# RoverWing-V095.net
KiCad netlist of a schematic drawn in EAGLE
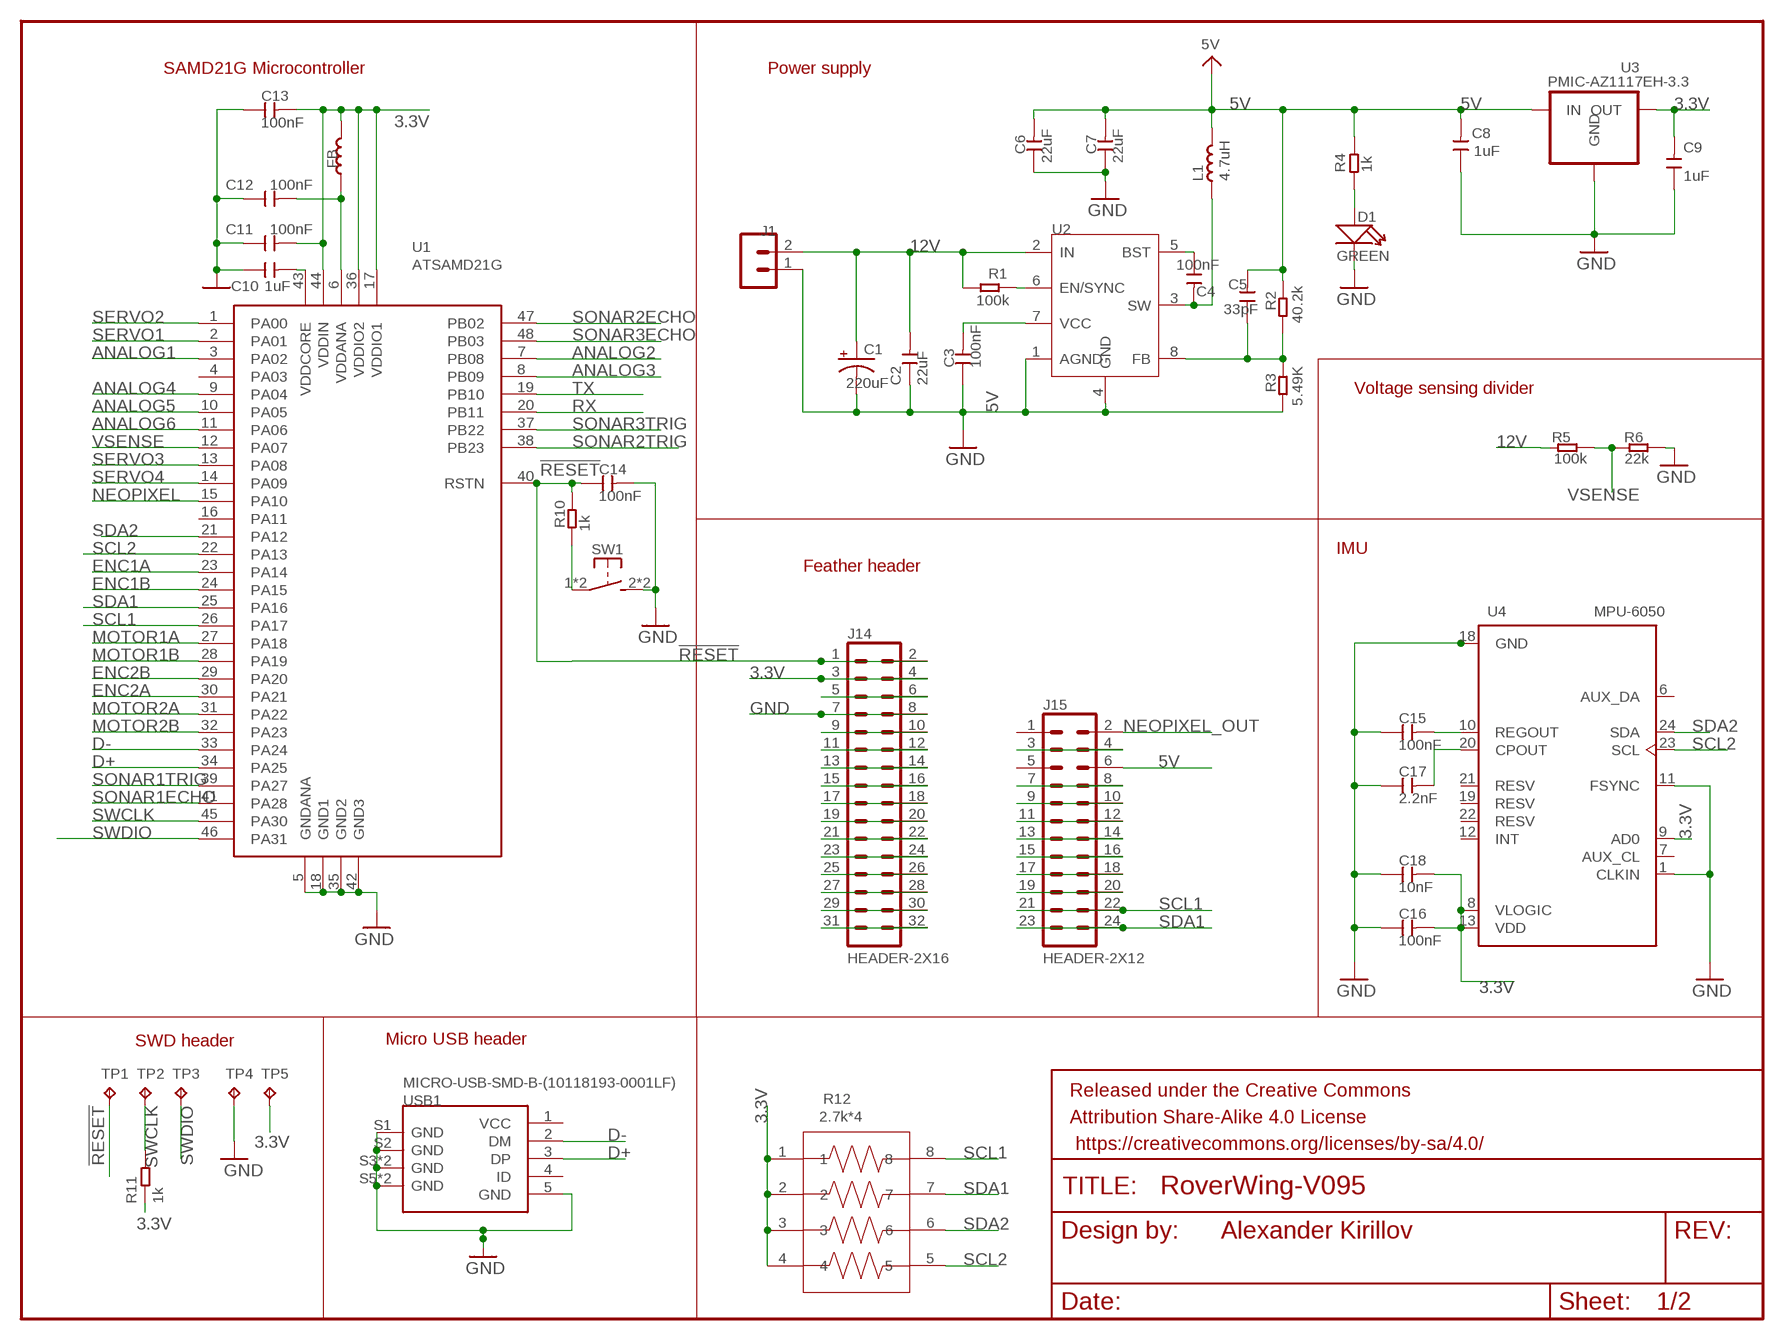
[diagram p0: schematic, sheet 1]
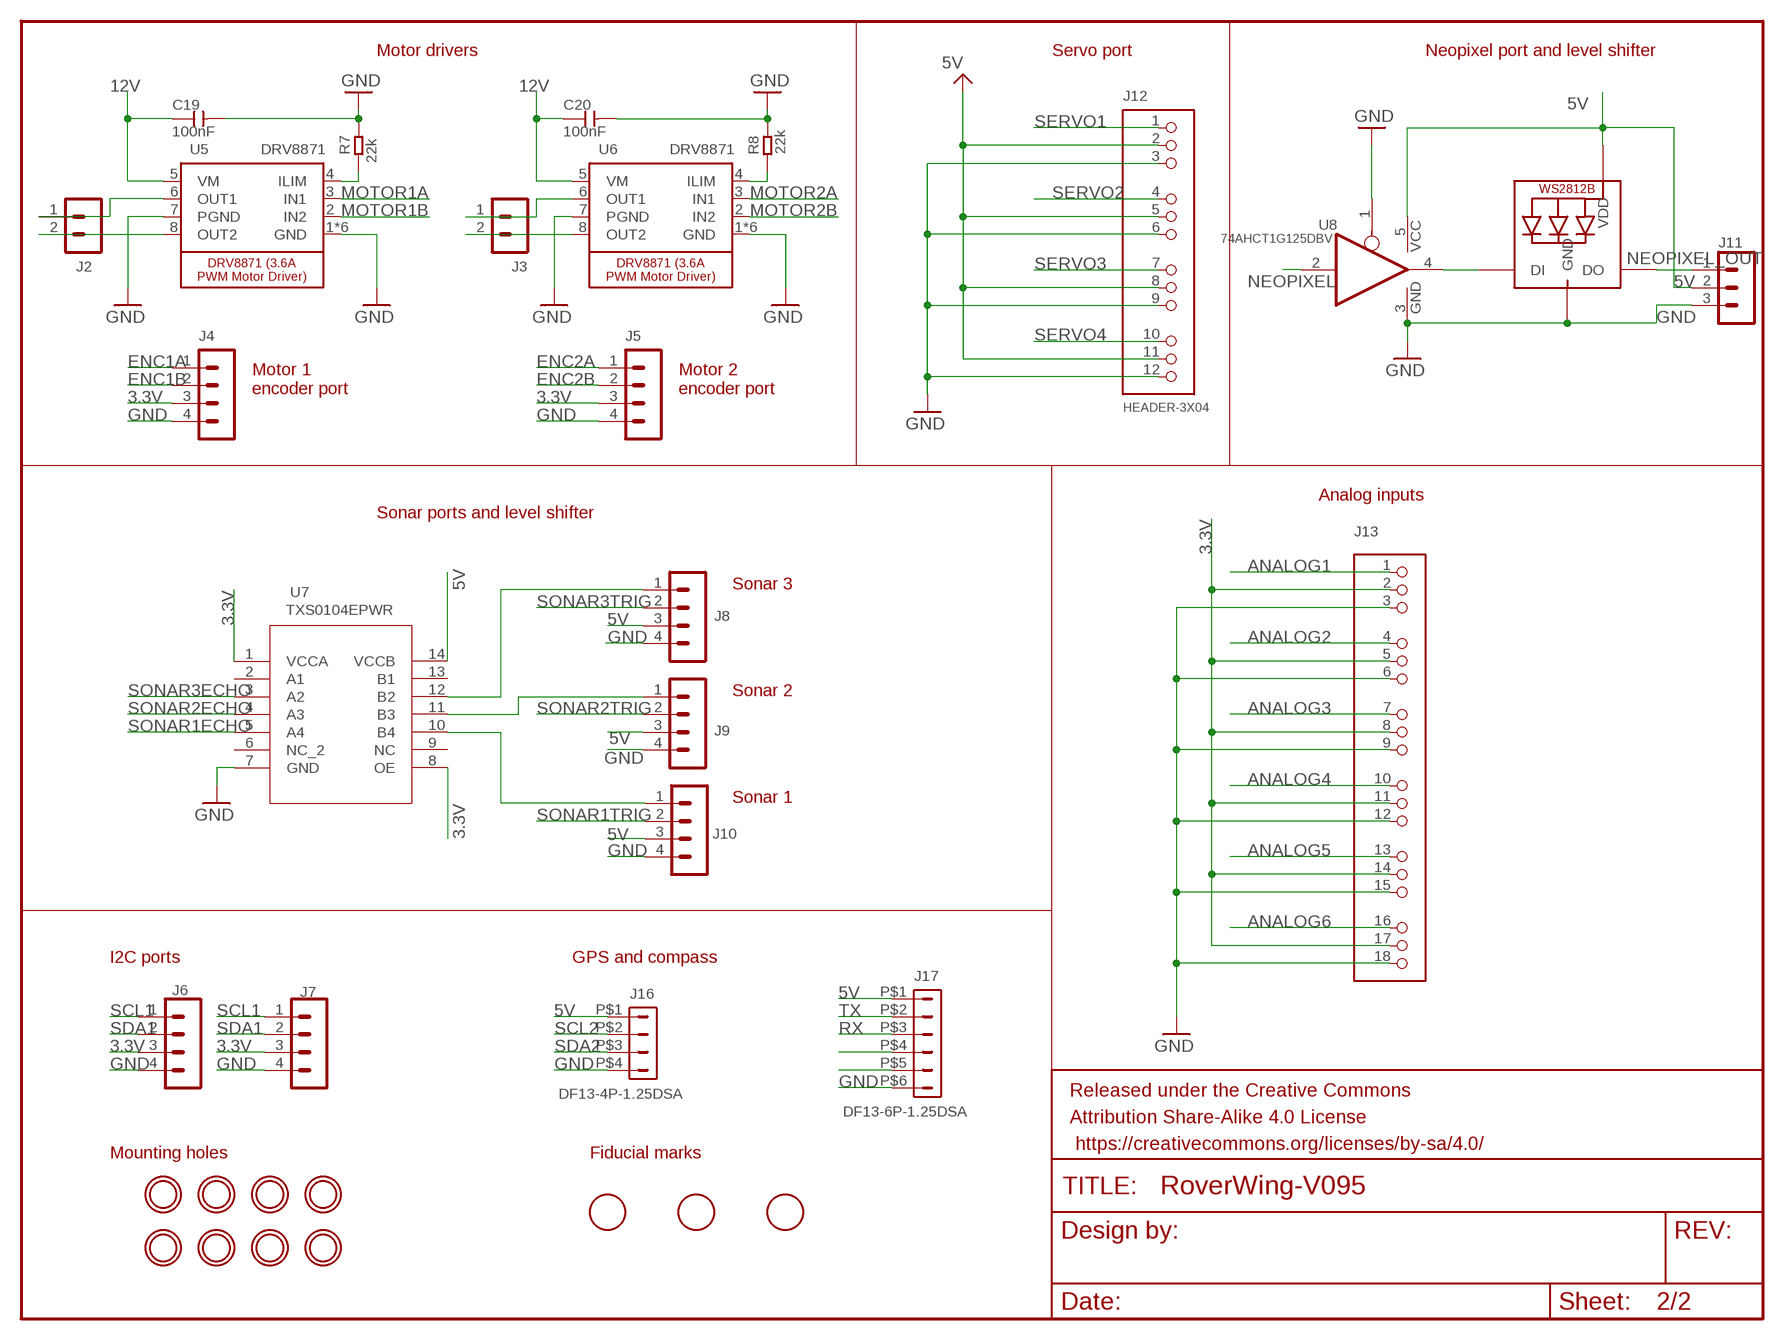
[diagram p1: schematic, sheet 2]

(export (version "E")
  (design (tool "Eeschema 10.0.6"))
  (components
    (comp (ref "C19")
      (value "100nF")
      (footprint "eagle-import:0805")
      (libsource (lib "eagle-import") (part "CAP-CERAMIC-SMD0805"))
    )
    (comp (ref "C20")
      (value "100nF")
      (footprint "eagle-import:0805")
      (libsource (lib "eagle-import") (part "CAP-CERAMIC-SMD0805"))
    )
    (comp (ref "FRAME1")
      (value "FRAME-LETTERNO_PACKAGE")
      (footprint "eagle-import:DUMMY")
      (libsource (lib "eagle-import") (part "FRAME-LETTERNO_PACKAGE"))
    )
    (comp (ref "J2")
      (value "HEADER-VH")
      (footprint "eagle-import:B2P-VH")
      (fields (field (name "PARTNO") "B2P-VH(LF)(SN)  "))
      (libsource (lib "eagle-import") (part "HEADER-VH"))
    )
    (comp (ref "J3")
      (value "HEADER-VH")
      (footprint "eagle-import:B2P-VH")
      (fields (field (name "PARTNO") "B2P-VH(LF)(SN)  "))
      (libsource (lib "eagle-import") (part "HEADER-VH"))
    )
    (comp (ref "J4")
      (value "HEADER-PH-4P")
      (footprint "eagle-import:B4B-PH-K")
      (fields (field (name "PARTNO") "B4B-PH-K-S(LF)(SN)"))
      (libsource (lib "eagle-import") (part "HEADER-PH-4P"))
    )
    (comp (ref "J5")
      (value "HEADER-PH-4P")
      (footprint "eagle-import:B4B-PH-K")
      (fields (field (name "PARTNO") "B4B-PH-K-S(LF)(SN)"))
      (libsource (lib "eagle-import") (part "HEADER-PH-4P"))
    )
    (comp (ref "J6")
      (value "HEADER-PH-4P")
      (footprint "eagle-import:B4B-PH-K")
      (fields (field (name "PARTNO") "B4B-PH-K-S(LF)(SN)"))
      (libsource (lib "eagle-import") (part "HEADER-PH-4P"))
    )
    (comp (ref "J7")
      (value "HEADER-PH-4P")
      (footprint "eagle-import:B4B-PH-K")
      (fields (field (name "PARTNO") "B4B-PH-K-S(LF)(SN)"))
      (libsource (lib "eagle-import") (part "HEADER-PH-4P"))
    )
    (comp (ref "J8")
      (value "HEADER-PH-4P")
      (footprint "eagle-import:B4B-PH-K")
      (fields (field (name "PARTNO") "B4B-PH-K-S(LF)(SN)"))
      (libsource (lib "eagle-import") (part "HEADER-PH-4P"))
    )
    (comp (ref "J9")
      (value "HEADER-PH-4P")
      (footprint "eagle-import:B4B-PH-K")
      (fields (field (name "PARTNO") "B4B-PH-K-S(LF)(SN)"))
      (libsource (lib "eagle-import") (part "HEADER-PH-4P"))
    )
    (comp (ref "J10")
      (value "HEADER-PH-4P")
      (footprint "eagle-import:B4B-PH-K")
      (fields (field (name "PARTNO") "B4B-PH-K-S(LF)(SN)"))
      (libsource (lib "eagle-import") (part "HEADER-PH-4P"))
    )
    (comp (ref "J11")
      (value "HEADER-PH-3P")
      (footprint "eagle-import:B3B-PH-K")
      (fields (field (name "PARTNO") "B3B-PH-K-S(LF)(SN)"))
      (libsource (lib "eagle-import") (part "HEADER-PH-3P"))
    )
    (comp (ref "J12")
      (value "HEADER-3X04")
      (footprint "eagle-import:3X04")
      (libsource (lib "eagle-import") (part "HEADER-3X04"))
    )
    (comp (ref "J13")
      (value "HEADER-3X06\"")
      (footprint "eagle-import:3X06")
      (libsource (lib "eagle-import") (part "HEADER-3X06{dblquote}"))
    )
    (comp (ref "J16")
      (value "DF13-4P-1.25DSA")
      (footprint "eagle-import:DF13-4P-1.25DSA")
      (libsource (lib "eagle-import") (part "DF13-4P-1.25DSA"))
    )
    (comp (ref "J17")
      (value "DF13-6P-1.25DSA")
      (footprint "eagle-import:DF13-6P-1.25DSA")
      (libsource (lib "eagle-import") (part "DF13-6P-1.25DSA"))
    )
    (comp (ref "LED1")
      (value "WS2812B3535")
      (footprint "eagle-import:LED3535")
      (fields (field (name "MANUFACTURER") "Worldsemi") (field (name "PARTNO") "WS2812B-3535 "))
      (libsource (lib "eagle-import") (part "WS2812B3535"))
    )
    (comp (ref "R7")
      (value "22k")
      (footprint "eagle-import:0805")
      (libsource (lib "eagle-import") (part "RES-SMD-0805"))
    )
    (comp (ref "R8")
      (value "22k")
      (footprint "eagle-import:0805")
      (libsource (lib "eagle-import") (part "RES-SMD-0805"))
    )
    (comp (ref "U$3")
      (value "MOUNTINGHOLE3.0_NPH")
      (footprint "eagle-import:MOUNTINGHOLE_3.0_NPH")
      (libsource (lib "eagle-import") (part "MOUNTINGHOLE3.0_NPH"))
    )
    (comp (ref "U$4")
      (value "MOUNTINGHOLE3.0_NPH")
      (footprint "eagle-import:MOUNTINGHOLE_3.0_NPH")
      (libsource (lib "eagle-import") (part "MOUNTINGHOLE3.0_NPH"))
    )
    (comp (ref "U$11")
      (value "FIDUCIAL")
      (footprint "eagle-import:FIDUCIAL_1MM")
      (libsource (lib "eagle-import") (part "FIDUCIAL"))
    )
    (comp (ref "U$13")
      (value "FIDUCIAL")
      (footprint "eagle-import:FIDUCIAL_1MM")
      (libsource (lib "eagle-import") (part "FIDUCIAL"))
    )
    (comp (ref "U$14")
      (value "MOUNTINGHOLE3.0_NPH")
      (footprint "eagle-import:MOUNTINGHOLE_3.0_NPH")
      (libsource (lib "eagle-import") (part "MOUNTINGHOLE3.0_NPH"))
    )
    (comp (ref "U$15")
      (value "MOUNTINGHOLE3.0_NPH")
      (footprint "eagle-import:MOUNTINGHOLE_3.0_NPH")
      (libsource (lib "eagle-import") (part "MOUNTINGHOLE3.0_NPH"))
    )
    (comp (ref "U$17")
      (value "FIDUCIAL")
      (footprint "eagle-import:FIDUCIAL_1MM")
      (libsource (lib "eagle-import") (part "FIDUCIAL"))
    )
    (comp (ref "U$24")
      (value "MOUNTINGHOLE3.0_NPH")
      (footprint "eagle-import:MOUNTINGHOLE_3.0_NPH")
      (libsource (lib "eagle-import") (part "MOUNTINGHOLE3.0_NPH"))
    )
    (comp (ref "U$25")
      (value "MOUNTINGHOLE3.0_NPH")
      (footprint "eagle-import:MOUNTINGHOLE_3.0_NPH")
      (libsource (lib "eagle-import") (part "MOUNTINGHOLE3.0_NPH"))
    )
    (comp (ref "U$26")
      (value "MOUNTINGHOLE3.0_NPH")
      (footprint "eagle-import:MOUNTINGHOLE_3.0_NPH")
      (libsource (lib "eagle-import") (part "MOUNTINGHOLE3.0_NPH"))
    )
    (comp (ref "U$27")
      (value "MOUNTINGHOLE3.0_NPH")
      (footprint "eagle-import:MOUNTINGHOLE_3.0_NPH")
      (libsource (lib "eagle-import") (part "MOUNTINGHOLE3.0_NPH"))
    )
    (comp (ref "U5")
      (value "DRV8871")
      (footprint "eagle-import:HSOP8")
      (fields (field (name "MANUFACTURER") "TEXAS INSTRUMENTS") (field (name "PARTNO") "DRV8871DDAR"))
      (libsource (lib "eagle-import") (part "DRV8871"))
    )
    (comp (ref "U6")
      (value "DRV8871")
      (footprint "eagle-import:HSOP8")
      (fields (field (name "MANUFACTURER") "TEXAS INSTRUMENTS") (field (name "PARTNO") "DRV8871DDAR"))
      (libsource (lib "eagle-import") (part "DRV8871"))
    )
    (comp (ref "U7")
      (value "TXS0104EPWR")
      (footprint "eagle-import:PW14")
      (fields (field (name "MANUFACTURER") "Texas Instruments"))
      (libsource (lib "eagle-import") (part "TXS0104EPWR"))
    )
    (comp (ref "U8")
      (value "74AHCT1G125DBV")
      (footprint "eagle-import:SOT23-5")
      (fields (field (name "PARTNO") "SN74AHCT1G125DBVR"))
      (libsource (lib "eagle-import") (part "741G125DBVAHCT"))
    )
    (comp (ref "C1")
      (value "220uF")
      (footprint "eagle-import:CAP-8X10.5")
      (libsource (lib "eagle-import") (part "CAP-POL-SMD-8X10.5"))
    )
    (comp (ref "C2")
      (value "22uF")
      (footprint "eagle-import:0805")
      (libsource (lib "eagle-import") (part "CAP-CERAMIC-SMD0805"))
    )
    (comp (ref "C3")
      (value "100nF")
      (footprint "eagle-import:0805")
      (libsource (lib "eagle-import") (part "CAP-CERAMIC-SMD0805"))
    )
    (comp (ref "C4")
      (value "100nF")
      (footprint "eagle-import:0805")
      (libsource (lib "eagle-import") (part "CAP-CERAMIC-SMD0805"))
    )
    (comp (ref "C5")
      (value "33pF")
      (footprint "eagle-import:0805")
      (libsource (lib "eagle-import") (part "CAP-CERAMIC-SMD0805"))
    )
    (comp (ref "C6")
      (value "22uF")
      (footprint "eagle-import:0805")
      (libsource (lib "eagle-import") (part "CAP-CERAMIC-SMD0805"))
    )
    (comp (ref "C7")
      (value "22uF")
      (footprint "eagle-import:0805")
      (libsource (lib "eagle-import") (part "CAP-CERAMIC-SMD0805"))
    )
    (comp (ref "C8")
      (value "1uF")
      (footprint "eagle-import:0805")
      (libsource (lib "eagle-import") (part "CAP-CERAMIC-SMD0805"))
    )
    (comp (ref "C9")
      (value "1uF")
      (footprint "eagle-import:0805")
      (libsource (lib "eagle-import") (part "CAP-CERAMIC-SMD0805"))
    )
    (comp (ref "C10")
      (value "1uF")
      (footprint "eagle-import:0805")
      (libsource (lib "eagle-import") (part "CAP-CERAMIC-SMD0805"))
    )
    (comp (ref "C11")
      (value "100nF")
      (footprint "eagle-import:0805")
      (libsource (lib "eagle-import") (part "CAP-CERAMIC-SMD0805"))
    )
    (comp (ref "C12")
      (value "100nF")
      (footprint "eagle-import:0805")
      (libsource (lib "eagle-import") (part "CAP-CERAMIC-SMD0805"))
    )
    (comp (ref "C13")
      (value "100nF")
      (footprint "eagle-import:0805")
      (libsource (lib "eagle-import") (part "CAP-CERAMIC-SMD0805"))
    )
    (comp (ref "C14")
      (value "100nF")
      (footprint "eagle-import:0805")
      (libsource (lib "eagle-import") (part "CAP-CERAMIC-SMD0805"))
    )
    (comp (ref "C15")
      (value "100nF")
      (footprint "eagle-import:0805")
      (libsource (lib "eagle-import") (part "CAP-CERAMIC-SMD0805"))
    )
    (comp (ref "C16")
      (value "100nF")
      (footprint "eagle-import:0805")
      (libsource (lib "eagle-import") (part "CAP-CERAMIC-SMD0805"))
    )
    (comp (ref "C17")
      (value "2.2nF")
      (footprint "eagle-import:0805")
      (libsource (lib "eagle-import") (part "CAP-CERAMIC-SMD0805"))
    )
    (comp (ref "C18")
      (value "10nF")
      (footprint "eagle-import:0805")
      (libsource (lib "eagle-import") (part "CAP-CERAMIC-SMD0805"))
    )
    (comp (ref "D1")
      (value "GREEN")
      (footprint "eagle-import:LED-0805")
      (libsource (lib "eagle-import") (part "SMD-LED-0805"))
    )
    (comp (ref "FB")
      (value "330R-1500MA")
      (footprint "eagle-import:0805")
      (fields (field (name "PARTNO") "BLM21PG331SN1D"))
      (libsource (lib "eagle-import") (part "SMD-FERRITE-BEAD-330R-1500MA(0805)"))
    )
    (comp (ref "FRAME2")
      (value "FRAME-LETTERNO_PACKAGE")
      (footprint "eagle-import:DUMMY")
      (libsource (lib "eagle-import") (part "FRAME-LETTERNO_PACKAGE"))
    )
    (comp (ref "J1")
      (value "HEADER-VH")
      (footprint "eagle-import:B2P-VH")
      (fields (field (name "PARTNO") "B2P-VH(LF)(SN)  "))
      (libsource (lib "eagle-import") (part "HEADER-VH"))
    )
    (comp (ref "J14")
      (value "HEADER-2X16")
      (footprint "eagle-import:2X16")
      (libsource (lib "eagle-import") (part "HEADER-2X16"))
    )
    (comp (ref "J15")
      (value "HEADER-2X12")
      (footprint "eagle-import:2X12")
      (libsource (lib "eagle-import") (part "HEADER-2X12"))
    )
    (comp (ref "L1")
      (value "4.7uH")
      (footprint "eagle-import:IND_TDK_7.1X6.5")
      (fields (field (name "MANUFACTURER") "TDK") (field (name "PARTNO") "SPM6530T-4R7M "))
      (libsource (lib "eagle-import") (part "IND-TDK-SPM6530T"))
    )
    (comp (ref "R1")
      (value "100k")
      (footprint "eagle-import:0805")
      (libsource (lib "eagle-import") (part "RES-SMD-0805"))
    )
    (comp (ref "R2")
      (value "40.2k")
      (footprint "eagle-import:0805")
      (libsource (lib "eagle-import") (part "RES-SMD-0805"))
    )
    (comp (ref "R3")
      (value "5.49K")
      (footprint "eagle-import:0805")
      (libsource (lib "eagle-import") (part "RES-SMD-0805"))
    )
    (comp (ref "R4")
      (value "1k")
      (footprint "eagle-import:0805")
      (libsource (lib "eagle-import") (part "RES-SMD-0805"))
    )
    (comp (ref "R5")
      (value "100k")
      (footprint "eagle-import:0805")
      (libsource (lib "eagle-import") (part "RES-SMD-0805"))
    )
    (comp (ref "R6")
      (value "22k")
      (footprint "eagle-import:0805")
      (libsource (lib "eagle-import") (part "RES-SMD-0805"))
    )
    (comp (ref "R10")
      (value "1k")
      (footprint "eagle-import:0805")
      (libsource (lib "eagle-import") (part "RES-SMD-0805"))
    )
    (comp (ref "R11")
      (value "1k")
      (footprint "eagle-import:0805")
      (libsource (lib "eagle-import") (part "RES-SMD-0805"))
    )
    (comp (ref "R12")
      (value "2.7k*4")
      (footprint "eagle-import:0603_4")
      (fields (field (name "PARTNO") "RTA03-4D272JTP "))
      (libsource (lib "eagle-import") (part "RES_ARRAY-2.7KX40603X4"))
    )
    (comp (ref "SW1")
      (value "SW-TACTILE-4.5X4.5_SMD")
      (footprint "eagle-import:TL3305")
      (fields (field (name "MANUFACTURER") "BRIGHT") (field (name "PARTNO") "TSA453G38-250 "))
      (libsource (lib "eagle-import") (part "SW-TACTILE-4.5X4.5_SMD"))
    )
    (comp (ref "TP1")
      (value "TPTP15R")
      (footprint "eagle-import:TP15R")
      (libsource (lib "eagle-import") (part "TPTP15R"))
    )
    (comp (ref "TP2")
      (value "TPTP15R")
      (footprint "eagle-import:TP15R")
      (libsource (lib "eagle-import") (part "TPTP15R"))
    )
    (comp (ref "TP3")
      (value "TPTP15R")
      (footprint "eagle-import:TP15R")
      (libsource (lib "eagle-import") (part "TPTP15R"))
    )
    (comp (ref "TP4")
      (value "TPTP15R")
      (footprint "eagle-import:TP15R")
      (libsource (lib "eagle-import") (part "TPTP15R"))
    )
    (comp (ref "TP5")
      (value "TPTP15R")
      (footprint "eagle-import:TP15R")
      (libsource (lib "eagle-import") (part "TPTP15R"))
    )
    (comp (ref "U1")
      (value "ATSAMD21G")
      (footprint "eagle-import:TQFP-48-EDITED")
      (fields (field (name "MANUFACTURER") "Microchip Technology") (field (name "PARTNO") "ATSAMD21G18A-AU"))
      (libsource (lib "eagle-import") (part "ATSAMD21G"))
    )
    (comp (ref "U2")
      (value "MP2225")
      (footprint "eagle-import:SOT-23-8")
      (fields (field (name "MANUFACTURER") "Monolithic Power Systems") (field (name "PARTNO") "MP2225GJ"))
      (libsource (lib "eagle-import") (part "PMIC-MP2225"))
    )
    (comp (ref "U3")
      (value "PMIC-AZ1117EH-3.3")
      (footprint "eagle-import:SOT223")
      (fields (field (name "PARTNO") "AZ1117EH-3.3TRG1"))
      (libsource (lib "eagle-import") (part "PMIC-AZ1117EH-3.3"))
    )
    (comp (ref "U4")
      (value "MPU-6050")
      (footprint "eagle-import:QFN50P400X400X95-24N")
      (fields (field (name "MANUFACTURER") "TDK InvenSense"))
      (libsource (lib "eagle-import") (part "MPU-6050"))
    )
    (comp (ref "USB1")
      (value "MICRO-USB-SMD-B-(10118193-0001LF)")
      (footprint "eagle-import:MICRO-USB5+6P-SMD-0.65-B")
      (fields (field (name "MANUFACTURER") "Amphenol ICC") (field (name "PARTNO") "10118193-0001LF"))
      (libsource (lib "eagle-import") (part "MICRO-USB-SMD-B-(10118193-0001LF)"))
    )
  )
  (nets
    (net (code "1") (name "3.3V") (class "Default")
      (node (ref "C11") (pin "2") (pinfunction "2_2") (pintype "passive"))
      (node (ref "C13") (pin "2") (pinfunction "2_2") (pintype "passive"))
      (node (ref "C16") (pin "2") (pinfunction "2_2") (pintype "passive"))
      (node (ref "C18") (pin "2") (pinfunction "2_2") (pintype "passive"))
      (node (ref "C9") (pin "2") (pinfunction "2_2") (pintype "passive"))
      (node (ref "FB") (pin "2") (pinfunction "2_2") (pintype "passive"))
      (node (ref "J13") (pin "11") (pinfunction "11_11") (pintype "passive"))
      (node (ref "J13") (pin "14") (pinfunction "14_14") (pintype "passive"))
      (node (ref "J13") (pin "17") (pinfunction "17_17") (pintype "passive"))
      (node (ref "J13") (pin "2") (pinfunction "2_2") (pintype "passive"))
      (node (ref "J13") (pin "5") (pinfunction "5_5") (pintype "passive"))
      (node (ref "J13") (pin "8") (pinfunction "8_8") (pintype "passive"))
      (node (ref "J14") (pin "3") (pinfunction "3_3") (pintype "passive"))
      (node (ref "J14") (pin "4") (pinfunction "4_4") (pintype "passive"))
      (node (ref "J4") (pin "3") (pinfunction "3_3") (pintype "passive"))
      (node (ref "J5") (pin "3") (pinfunction "3_3") (pintype "passive"))
      (node (ref "J6") (pin "3") (pinfunction "3_3") (pintype "passive"))
      (node (ref "J7") (pin "3") (pinfunction "3_3") (pintype "passive"))
      (node (ref "R11") (pin "1") (pinfunction "1_1") (pintype "passive"))
      (node (ref "R12") (pin "1") (pinfunction "1_1") (pintype "passive"))
      (node (ref "R12") (pin "2") (pinfunction "2_2") (pintype "passive"))
      (node (ref "R12") (pin "3") (pinfunction "3_3") (pintype "passive"))
      (node (ref "R12") (pin "4") (pinfunction "4_4") (pintype "passive"))
      (node (ref "TP5") (pin "TP") (pinfunction "TP_TP") (pintype "input"))
      (node (ref "U1") (pin "17") (pinfunction "VDDIO1_17") (pintype "power_in"))
      (node (ref "U1") (pin "36") (pinfunction "VDDIO2_36") (pintype "power_in"))
      (node (ref "U1") (pin "44") (pinfunction "VDDIN_44") (pintype "power_in"))
      (node (ref "U3") (pin "2") (pinfunction "OUT_2") (pintype "output"))
      (node (ref "U3") (pin "4") (pinfunction "OUT_4") (pintype "output"))
      (node (ref "U4") (pin "13") (pinfunction "VDD_13") (pintype "power_in"))
      (node (ref "U4") (pin "8") (pinfunction "VLOGIC_8") (pintype "power_in"))
      (node (ref "U4") (pin "9") (pinfunction "AD0_9") (pintype "input"))
      (node (ref "U7") (pin "1") (pinfunction "VCCA_1") (pintype "power_in"))
      (node (ref "U7") (pin "8") (pinfunction "OE_8") (pintype "output"))
    )
    (net (code "2") (name "5V") (class "Default")
      (node (ref "C5") (pin "2") (pinfunction "2_2") (pintype "passive"))
      (node (ref "C6") (pin "2") (pinfunction "2_2") (pintype "passive"))
      (node (ref "C7") (pin "2") (pinfunction "2_2") (pintype "passive"))
      (node (ref "C8") (pin "2") (pinfunction "2_2") (pintype "passive"))
      (node (ref "J10") (pin "3") (pinfunction "3_3") (pintype "passive"))
      (node (ref "J11") (pin "2") (pinfunction "2_2") (pintype "passive"))
      (node (ref "J12") (pin "11") (pinfunction "11_11") (pintype "passive"))
      (node (ref "J12") (pin "2") (pinfunction "2_2") (pintype "passive"))
      (node (ref "J12") (pin "5") (pinfunction "5_5") (pintype "passive"))
      (node (ref "J12") (pin "8") (pinfunction "8_8") (pintype "passive"))
      (node (ref "J15") (pin "6") (pinfunction "6_6") (pintype "passive"))
      (node (ref "J16") (pin "P$1") (pinfunction "1_P$1") (pintype "passive"))
      (node (ref "J17") (pin "P$1") (pinfunction "1_P$1") (pintype "passive"))
      (node (ref "J8") (pin "3") (pinfunction "3_3") (pintype "passive"))
      (node (ref "J9") (pin "3") (pinfunction "3_3") (pintype "passive"))
      (node (ref "L1") (pin "2") (pinfunction "2_2") (pintype "passive"))
      (node (ref "LED1") (pin "3") (pinfunction "VDD_3") (pintype "power_in"))
      (node (ref "R2") (pin "1") (pinfunction "1_1") (pintype "passive"))
      (node (ref "R4") (pin "2") (pinfunction "2_2") (pintype "passive"))
      (node (ref "U3") (pin "3") (pinfunction "IN_3") (pintype "input"))
      (node (ref "U7") (pin "14") (pinfunction "VCCB_14") (pintype "power_in"))
      (node (ref "U8") (pin "5") (pinfunction "VCC_5") (pintype "power_in"))
    )
    (net (code "3") (name "12V") (class "Default")
      (node (ref "C1") (pin "+") (pinfunction "+_+") (pintype "passive"))
      (node (ref "C19") (pin "1") (pinfunction "1_1") (pintype "passive"))
      (node (ref "C2") (pin "2") (pinfunction "2_2") (pintype "passive"))
      (node (ref "C20") (pin "1") (pinfunction "1_1") (pintype "passive"))
      (node (ref "J1") (pin "2") (pinfunction "2_2") (pintype "passive"))
      (node (ref "R1") (pin "2") (pinfunction "2_2") (pintype "passive"))
      (node (ref "R5") (pin "2") (pinfunction "2_2") (pintype "passive"))
      (node (ref "U2") (pin "2") (pinfunction "IN_2") (pintype "bidirectional"))
      (node (ref "U5") (pin "5") (pinfunction "VM_5") (pintype "power_in"))
      (node (ref "U6") (pin "5") (pinfunction "VM_5") (pintype "power_in"))
    )
    (net (code "4") (name "ANALOG1") (class "Default")
      (node (ref "J13") (pin "1") (pinfunction "1_1") (pintype "passive"))
      (node (ref "U1") (pin "3") (pinfunction "PA02_3") (pintype "bidirectional"))
    )
    (net (code "5") (name "ANALOG2") (class "Default")
      (node (ref "J13") (pin "4") (pinfunction "4_4") (pintype "passive"))
      (node (ref "U1") (pin "7") (pinfunction "PB08_7") (pintype "bidirectional"))
    )
    (net (code "6") (name "ANALOG3") (class "Default")
      (node (ref "J13") (pin "7") (pinfunction "7_7") (pintype "passive"))
      (node (ref "U1") (pin "8") (pinfunction "PB09_8") (pintype "bidirectional"))
    )
    (net (code "7") (name "ANALOG4") (class "Default")
      (node (ref "J13") (pin "10") (pinfunction "10_10") (pintype "passive"))
      (node (ref "U1") (pin "9") (pinfunction "PA04_9") (pintype "bidirectional"))
    )
    (net (code "8") (name "ANALOG5") (class "Default")
      (node (ref "J13") (pin "13") (pinfunction "13_13") (pintype "passive"))
      (node (ref "U1") (pin "10") (pinfunction "PA05_10") (pintype "bidirectional"))
    )
    (net (code "9") (name "ANALOG6") (class "Default")
      (node (ref "J13") (pin "16") (pinfunction "16_16") (pintype "passive"))
      (node (ref "U1") (pin "11") (pinfunction "PA06_11") (pintype "bidirectional"))
    )
    (net (code "10") (name "D+") (class "Default")
      (node (ref "U1") (pin "34") (pinfunction "PA25_34") (pintype "bidirectional"))
      (node (ref "USB1") (pin "3") (pinfunction "DP_3") (pintype "bidirectional"))
    )
    (net (code "11") (name "D-") (class "Default")
      (node (ref "U1") (pin "33") (pinfunction "PA24_33") (pintype "bidirectional"))
      (node (ref "USB1") (pin "2") (pinfunction "DM_2") (pintype "bidirectional"))
    )
    (net (code "12") (name "ENC1A") (class "Default")
      (node (ref "J4") (pin "1") (pinfunction "1_1") (pintype "passive"))
      (node (ref "U1") (pin "23") (pinfunction "PA14_23") (pintype "bidirectional"))
    )
    (net (code "13") (name "ENC1B") (class "Default")
      (node (ref "J4") (pin "2") (pinfunction "2_2") (pintype "passive"))
      (node (ref "U1") (pin "24") (pinfunction "PA15_24") (pintype "bidirectional"))
    )
    (net (code "14") (name "ENC2A") (class "Default")
      (node (ref "J5") (pin "1") (pinfunction "1_1") (pintype "passive"))
      (node (ref "U1") (pin "30") (pinfunction "PA21_30") (pintype "bidirectional"))
    )
    (net (code "15") (name "ENC2B") (class "Default")
      (node (ref "J5") (pin "2") (pinfunction "2_2") (pintype "passive"))
      (node (ref "U1") (pin "29") (pinfunction "PA20_29") (pintype "bidirectional"))
    )
    (net (code "16") (name "GND") (class "Default")
      (node (ref "C1") (pin "-") (pinfunction "-_-") (pintype "passive"))
      (node (ref "C10") (pin "1") (pinfunction "1_1") (pintype "passive"))
      (node (ref "C11") (pin "1") (pinfunction "1_1") (pintype "passive"))
      (node (ref "C12") (pin "1") (pinfunction "1_1") (pintype "passive"))
      (node (ref "C13") (pin "1") (pinfunction "1_1") (pintype "passive"))
      (node (ref "C14") (pin "2") (pinfunction "2_2") (pintype "passive"))
      (node (ref "C15") (pin "1") (pinfunction "1_1") (pintype "passive"))
      (node (ref "C16") (pin "1") (pinfunction "1_1") (pintype "passive"))
      (node (ref "C17") (pin "1") (pinfunction "1_1") (pintype "passive"))
      (node (ref "C18") (pin "1") (pinfunction "1_1") (pintype "passive"))
      (node (ref "C19") (pin "2") (pinfunction "2_2") (pintype "passive"))
      (node (ref "C2") (pin "1") (pinfunction "1_1") (pintype "passive"))
      (node (ref "C20") (pin "2") (pinfunction "2_2") (pintype "passive"))
      (node (ref "C3") (pin "1") (pinfunction "1_1") (pintype "passive"))
      (node (ref "C6") (pin "1") (pinfunction "1_1") (pintype "passive"))
      (node (ref "C7") (pin "1") (pinfunction "1_1") (pintype "passive"))
      (node (ref "C8") (pin "1") (pinfunction "1_1") (pintype "passive"))
      (node (ref "C9") (pin "1") (pinfunction "1_1") (pintype "passive"))
      (node (ref "D1") (pin "-") (pinfunction "-_-") (pintype "passive"))
      (node (ref "J1") (pin "1") (pinfunction "1_1") (pintype "passive"))
      (node (ref "J10") (pin "4") (pinfunction "4_4") (pintype "passive"))
      (node (ref "J11") (pin "3") (pinfunction "3_3") (pintype "passive"))
      (node (ref "J12") (pin "12") (pinfunction "12_12") (pintype "passive"))
      (node (ref "J12") (pin "3") (pinfunction "3_3") (pintype "passive"))
      (node (ref "J12") (pin "6") (pinfunction "6_6") (pintype "passive"))
      (node (ref "J12") (pin "9") (pinfunction "9_9") (pintype "passive"))
      (node (ref "J13") (pin "12") (pinfunction "12_12") (pintype "passive"))
      (node (ref "J13") (pin "15") (pinfunction "15_15") (pintype "passive"))
      (node (ref "J13") (pin "18") (pinfunction "18_18") (pintype "passive"))
      (node (ref "J13") (pin "3") (pinfunction "3_3") (pintype "passive"))
      (node (ref "J13") (pin "6") (pinfunction "6_6") (pintype "passive"))
      (node (ref "J13") (pin "9") (pinfunction "9_9") (pintype "passive"))
      (node (ref "J14") (pin "7") (pinfunction "7_7") (pintype "passive"))
      (node (ref "J14") (pin "8") (pinfunction "8_8") (pintype "passive"))
      (node (ref "J16") (pin "P$4") (pinfunction "4_P$4") (pintype "passive"))
      (node (ref "J17") (pin "P$6") (pinfunction "6_P$6") (pintype "passive"))
      (node (ref "J4") (pin "4") (pinfunction "4_4") (pintype "passive"))
      (node (ref "J5") (pin "4") (pinfunction "4_4") (pintype "passive"))
      (node (ref "J6") (pin "4") (pinfunction "4_4") (pintype "passive"))
      (node (ref "J7") (pin "4") (pinfunction "4_4") (pintype "passive"))
      (node (ref "J8") (pin "4") (pinfunction "4_4") (pintype "passive"))
      (node (ref "J9") (pin "4") (pinfunction "4_4") (pintype "passive"))
      (node (ref "LED1") (pin "1") (pinfunction "GND_1") (pintype "power_in"))
      (node (ref "R3") (pin "2") (pinfunction "2_2") (pintype "passive"))
      (node (ref "R6") (pin "2") (pinfunction "2_2") (pintype "passive"))
      (node (ref "R7") (pin "2") (pinfunction "2_2") (pintype "passive"))
      (node (ref "R8") (pin "2") (pinfunction "2_2") (pintype "passive"))
      (node (ref "SW1") (pin "2") (pinfunction "S1_2") (pintype "passive"))
      (node (ref "SW1") (pin "3") (pinfunction "S1_3") (pintype "passive"))
      (node (ref "TP4") (pin "TP") (pinfunction "TP_TP") (pintype "input"))
      (node (ref "U1") (pin "18") (pinfunction "GND1_18") (pintype "power_in"))
      (node (ref "U1") (pin "35") (pinfunction "GND2_35") (pintype "power_in"))
      (node (ref "U1") (pin "42") (pinfunction "GND3_42") (pintype "power_in"))
      (node (ref "U1") (pin "5") (pinfunction "GNDANA_5") (pintype "power_in"))
      (node (ref "U2") (pin "1") (pinfunction "AGND_1") (pintype "bidirectional"))
      (node (ref "U2") (pin "4") (pinfunction "GND_4") (pintype "bidirectional"))
      (node (ref "U3") (pin "1") (pinfunction "GND_1") (pintype "power_in"))
      (node (ref "U4") (pin "1") (pinfunction "CLKIN_1") (pintype "input"))
      (node (ref "U4") (pin "11") (pinfunction "FSYNC_11") (pintype "input"))
      (node (ref "U4") (pin "18") (pinfunction "GND_18") (pintype "power_in"))
      (node (ref "U5") (pin "1") (pinfunction "GND_1") (pintype "power_in"))
      (node (ref "U5") (pin "7") (pinfunction "PGND_7") (pintype "power_in"))
      (node (ref "U5") (pin "GND") (pinfunction "GND_GND") (pintype "power_in"))
      (node (ref "U5") (pin "P$1") (pinfunction "GND_P$1") (pintype "power_in"))
      (node (ref "U5") (pin "P$2") (pinfunction "GND_P$2") (pintype "power_in"))
      (node (ref "U5") (pin "P$3") (pinfunction "GND_P$3") (pintype "power_in"))
      (node (ref "U5") (pin "P$4") (pinfunction "GND_P$4") (pintype "power_in"))
      (node (ref "U6") (pin "1") (pinfunction "GND_1") (pintype "power_in"))
      (node (ref "U6") (pin "7") (pinfunction "PGND_7") (pintype "power_in"))
      (node (ref "U6") (pin "GND") (pinfunction "GND_GND") (pintype "power_in"))
      (node (ref "U6") (pin "P$1") (pinfunction "GND_P$1") (pintype "power_in"))
      (node (ref "U6") (pin "P$2") (pinfunction "GND_P$2") (pintype "power_in"))
      (node (ref "U6") (pin "P$3") (pinfunction "GND_P$3") (pintype "power_in"))
      (node (ref "U6") (pin "P$4") (pinfunction "GND_P$4") (pintype "power_in"))
      (node (ref "U7") (pin "7") (pinfunction "GND_7") (pintype "power_in"))
      (node (ref "U8") (pin "1") (pinfunction "OE_1") (pintype "input"))
      (node (ref "U8") (pin "3") (pinfunction "GND_3") (pintype "power_in"))
      (node (ref "USB1") (pin "5") (pinfunction "GND_5") (pintype "bidirectional"))
      (node (ref "USB1") (pin "S1") (pinfunction "GND_S1") (pintype "bidirectional"))
      (node (ref "USB1") (pin "S2") (pinfunction "GND_S2") (pintype "bidirectional"))
      (node (ref "USB1") (pin "S3") (pinfunction "GND_S3") (pintype "bidirectional"))
      (node (ref "USB1") (pin "S4") (pinfunction "GND_S4") (pintype "bidirectional"))
      (node (ref "USB1") (pin "S5") (pinfunction "GND_S5") (pintype "bidirectional"))
      (node (ref "USB1") (pin "S6") (pinfunction "GND_S6") (pintype "bidirectional"))
    )
    (net (code "17") (name "MOTOR1A") (class "Default")
      (node (ref "U1") (pin "27") (pinfunction "PA18_27") (pintype "bidirectional"))
      (node (ref "U5") (pin "3") (pinfunction "IN1_3") (pintype "input"))
    )
    (net (code "18") (name "MOTOR1B") (class "Default")
      (node (ref "U1") (pin "28") (pinfunction "PA19_28") (pintype "bidirectional"))
      (node (ref "U5") (pin "2") (pinfunction "IN2_2") (pintype "input"))
    )
    (net (code "19") (name "MOTOR2A") (class "Default")
      (node (ref "U1") (pin "31") (pinfunction "PA22_31") (pintype "bidirectional"))
      (node (ref "U6") (pin "3") (pinfunction "IN1_3") (pintype "input"))
    )
    (net (code "20") (name "MOTOR2B") (class "Default")
      (node (ref "U1") (pin "32") (pinfunction "PA23_32") (pintype "bidirectional"))
      (node (ref "U6") (pin "2") (pinfunction "IN2_2") (pintype "input"))
    )
    (net (code "21") (name "NEOPIXEL") (class "Default")
      (node (ref "U1") (pin "15") (pinfunction "PA10_15") (pintype "bidirectional"))
      (node (ref "U8") (pin "2") (pinfunction "I_2") (pintype "input"))
    )
    (net (code "22") (name "NEOPIXEL_OUT") (class "Default")
      (node (ref "J11") (pin "1") (pinfunction "1_1") (pintype "passive"))
      (node (ref "J15") (pin "2") (pinfunction "2_2") (pintype "passive"))
      (node (ref "LED1") (pin "4") (pinfunction "DO_4") (pintype "output"))
    )
    (net (code "23") (name "Net-(D1-Pad+)") (class "Default")
      (node (ref "D1") (pin "+") (pinfunction "+_+") (pintype "passive"))
      (node (ref "R4") (pin "1") (pinfunction "1_1") (pintype "passive"))
    )
    (net (code "24") (name "Net-(J14-Pad5)") (class "Default")
      (node (ref "J14") (pin "5") (pinfunction "5_5") (pintype "passive"))
      (node (ref "J14") (pin "6") (pinfunction "6_6") (pintype "passive"))
    )
    (net (code "25") (name "Net-(J14-Pad10)") (class "Default")
      (node (ref "J14") (pin "10") (pinfunction "10_10") (pintype "passive"))
      (node (ref "J14") (pin "9") (pinfunction "9_9") (pintype "passive"))
    )
    (net (code "26") (name "Net-(J14-Pad11)") (class "Default")
      (node (ref "J14") (pin "11") (pinfunction "11_11") (pintype "passive"))
      (node (ref "J14") (pin "12") (pinfunction "12_12") (pintype "passive"))
    )
    (net (code "27") (name "Net-(J14-Pad13)") (class "Default")
      (node (ref "J14") (pin "13") (pinfunction "13_13") (pintype "passive"))
      (node (ref "J14") (pin "14") (pinfunction "14_14") (pintype "passive"))
    )
    (net (code "28") (name "Net-(J14-Pad15)") (class "Default")
      (node (ref "J14") (pin "15") (pinfunction "15_15") (pintype "passive"))
      (node (ref "J14") (pin "16") (pinfunction "16_16") (pintype "passive"))
    )
    (net (code "29") (name "Net-(J14-Pad17)") (class "Default")
      (node (ref "J14") (pin "17") (pinfunction "17_17") (pintype "passive"))
      (node (ref "J14") (pin "18") (pinfunction "18_18") (pintype "passive"))
    )
    (net (code "30") (name "Net-(J14-Pad19)") (class "Default")
      (node (ref "J14") (pin "19") (pinfunction "19_19") (pintype "passive"))
      (node (ref "J14") (pin "20") (pinfunction "20_20") (pintype "passive"))
    )
    (net (code "31") (name "Net-(J14-Pad21)") (class "Default")
      (node (ref "J14") (pin "21") (pinfunction "21_21") (pintype "passive"))
      (node (ref "J14") (pin "22") (pinfunction "22_22") (pintype "passive"))
    )
    (net (code "32") (name "Net-(J14-Pad23)") (class "Default")
      (node (ref "J14") (pin "23") (pinfunction "23_23") (pintype "passive"))
      (node (ref "J14") (pin "24") (pinfunction "24_24") (pintype "passive"))
    )
    (net (code "33") (name "Net-(J14-Pad25)") (class "Default")
      (node (ref "J14") (pin "25") (pinfunction "25_25") (pintype "passive"))
      (node (ref "J14") (pin "26") (pinfunction "26_26") (pintype "passive"))
    )
    (net (code "34") (name "Net-(J14-Pad27)") (class "Default")
      (node (ref "J14") (pin "27") (pinfunction "27_27") (pintype "passive"))
      (node (ref "J14") (pin "28") (pinfunction "28_28") (pintype "passive"))
    )
    (net (code "35") (name "Net-(J14-Pad29)") (class "Default")
      (node (ref "J14") (pin "29") (pinfunction "29_29") (pintype "passive"))
      (node (ref "J14") (pin "30") (pinfunction "30_30") (pintype "passive"))
    )
    (net (code "36") (name "Net-(J14-Pad31)") (class "Default")
      (node (ref "J14") (pin "31") (pinfunction "31_31") (pintype "passive"))
      (node (ref "J14") (pin "32") (pinfunction "32_32") (pintype "passive"))
    )
    (net (code "37") (name "Net-(J15-Pad3)") (class "Default")
      (node (ref "J15") (pin "3") (pinfunction "3_3") (pintype "passive"))
      (node (ref "J15") (pin "4") (pinfunction "4_4") (pintype "passive"))
    )
    (net (code "38") (name "Net-(J15-Pad7)") (class "Default")
      (node (ref "J15") (pin "7") (pinfunction "7_7") (pintype "passive"))
      (node (ref "J15") (pin "8") (pinfunction "8_8") (pintype "passive"))
    )
    (net (code "39") (name "Net-(J15-Pad10)") (class "Default")
      (node (ref "J15") (pin "10") (pinfunction "10_10") (pintype "passive"))
      (node (ref "J15") (pin "9") (pinfunction "9_9") (pintype "passive"))
    )
    (net (code "40") (name "Net-(J15-Pad11)") (class "Default")
      (node (ref "J15") (pin "11") (pinfunction "11_11") (pintype "passive"))
      (node (ref "J15") (pin "12") (pinfunction "12_12") (pintype "passive"))
    )
    (net (code "41") (name "Net-(J15-Pad13)") (class "Default")
      (node (ref "J15") (pin "13") (pinfunction "13_13") (pintype "passive"))
      (node (ref "J15") (pin "14") (pinfunction "14_14") (pintype "passive"))
    )
    (net (code "42") (name "Net-(J15-Pad15)") (class "Default")
      (node (ref "J15") (pin "15") (pinfunction "15_15") (pintype "passive"))
      (node (ref "J15") (pin "16") (pinfunction "16_16") (pintype "passive"))
    )
    (net (code "43") (name "Net-(J15-Pad17)") (class "Default")
      (node (ref "J15") (pin "17") (pinfunction "17_17") (pintype "passive"))
      (node (ref "J15") (pin "18") (pinfunction "18_18") (pintype "passive"))
    )
    (net (code "44") (name "Net-(J15-Pad19)") (class "Default")
      (node (ref "J15") (pin "19") (pinfunction "19_19") (pintype "passive"))
      (node (ref "J15") (pin "20") (pinfunction "20_20") (pintype "passive"))
    )
    (net (code "45") (name "Net-(LED1-DI)") (class "Default")
      (node (ref "LED1") (pin "2") (pinfunction "DI_2") (pintype "input"))
      (node (ref "U8") (pin "4") (pinfunction "O_4") (pintype "tri_state"))
    )
    (net (code "46") (name "Net-(R10-Pad1)") (class "Default")
      (node (ref "R10") (pin "1") (pinfunction "1_1") (pintype "passive"))
      (node (ref "SW1") (pin "1") (pinfunction "P1_1") (pintype "passive"))
      (node (ref "SW1") (pin "4") (pinfunction "P1_4") (pintype "passive"))
    )
    (net (code "47") (name "Net-(U1-VDDANA)") (class "Default")
      (node (ref "C12") (pin "2") (pinfunction "2_2") (pintype "passive"))
      (node (ref "FB") (pin "1") (pinfunction "1_1") (pintype "passive"))
      (node (ref "U1") (pin "6") (pinfunction "VDDANA_6") (pintype "power_in"))
    )
    (net (code "48") (name "Net-(U1-VDDCORE)") (class "Default")
      (node (ref "C10") (pin "2") (pinfunction "2_2") (pintype "passive"))
      (node (ref "U1") (pin "43") (pinfunction "VDDCORE_43") (pintype "power_in"))
    )
    (net (code "49") (name "Net-(U2-BST)") (class "Default")
      (node (ref "C4") (pin "1") (pinfunction "1_1") (pintype "passive"))
      (node (ref "U2") (pin "5") (pinfunction "BST_5") (pintype "bidirectional"))
    )
    (net (code "50") (name "Net-(U2-EN{slash}SYNC)") (class "Default")
      (node (ref "R1") (pin "1") (pinfunction "1_1") (pintype "passive"))
      (node (ref "U2") (pin "6") (pinfunction "EN/SYNC_6") (pintype "bidirectional"))
    )
    (net (code "51") (name "Net-(U2-FB)") (class "Default")
      (node (ref "C5") (pin "1") (pinfunction "1_1") (pintype "passive"))
      (node (ref "R2") (pin "2") (pinfunction "2_2") (pintype "passive"))
      (node (ref "R3") (pin "1") (pinfunction "1_1") (pintype "passive"))
      (node (ref "U2") (pin "8") (pinfunction "FB_8") (pintype "bidirectional"))
    )
    (net (code "52") (name "Net-(U2-SW)") (class "Default")
      (node (ref "C4") (pin "2") (pinfunction "2_2") (pintype "passive"))
      (node (ref "L1") (pin "1") (pinfunction "1_1") (pintype "passive"))
      (node (ref "U2") (pin "3") (pinfunction "SW_3") (pintype "bidirectional"))
    )
    (net (code "53") (name "Net-(U2-VCC)") (class "Default")
      (node (ref "C3") (pin "2") (pinfunction "2_2") (pintype "passive"))
      (node (ref "U2") (pin "7") (pinfunction "VCC_7") (pintype "bidirectional"))
    )
    (net (code "54") (name "Net-(U4-CPOUT)") (class "Default")
      (node (ref "C17") (pin "2") (pinfunction "2_2") (pintype "passive"))
      (node (ref "U4") (pin "20") (pinfunction "CPOUT_20") (pintype "passive"))
    )
    (net (code "55") (name "Net-(U4-REGOUT)") (class "Default")
      (node (ref "C15") (pin "2") (pinfunction "2_2") (pintype "passive"))
      (node (ref "U4") (pin "10") (pinfunction "REGOUT_10") (pintype "passive"))
    )
    (net (code "56") (name "Net-(U5-ILIM)") (class "Default")
      (node (ref "R7") (pin "1") (pinfunction "1_1") (pintype "passive"))
      (node (ref "U5") (pin "4") (pinfunction "ILIM_4") (pintype "input"))
    )
    (net (code "57") (name "Net-(U5-OUT1)") (class "Default")
      (node (ref "J2") (pin "1") (pinfunction "1_1") (pintype "passive"))
      (node (ref "U5") (pin "6") (pinfunction "OUT1_6") (pintype "output"))
    )
    (net (code "58") (name "Net-(U5-OUT2)") (class "Default")
      (node (ref "J2") (pin "2") (pinfunction "2_2") (pintype "passive"))
      (node (ref "U5") (pin "8") (pinfunction "OUT2_8") (pintype "output"))
    )
    (net (code "59") (name "Net-(U6-ILIM)") (class "Default")
      (node (ref "R8") (pin "1") (pinfunction "1_1") (pintype "passive"))
      (node (ref "U6") (pin "4") (pinfunction "ILIM_4") (pintype "input"))
    )
    (net (code "60") (name "Net-(U6-OUT1)") (class "Default")
      (node (ref "J3") (pin "1") (pinfunction "1_1") (pintype "passive"))
      (node (ref "U6") (pin "6") (pinfunction "OUT1_6") (pintype "output"))
    )
    (net (code "61") (name "Net-(U6-OUT2)") (class "Default")
      (node (ref "J3") (pin "2") (pinfunction "2_2") (pintype "passive"))
      (node (ref "U6") (pin "8") (pinfunction "OUT2_8") (pintype "output"))
    )
    (net (code "62") (name "Net-(U7-B2)") (class "Default")
      (node (ref "J8") (pin "1") (pinfunction "1_1") (pintype "passive"))
      (node (ref "U7") (pin "12") (pinfunction "B2_12") (pintype "bidirectional"))
    )
    (net (code "63") (name "Net-(U7-B3)") (class "Default")
      (node (ref "J9") (pin "1") (pinfunction "1_1") (pintype "passive"))
      (node (ref "U7") (pin "11") (pinfunction "B3_11") (pintype "bidirectional"))
    )
    (net (code "64") (name "Net-(U7-B4)") (class "Default")
      (node (ref "J10") (pin "1") (pinfunction "1_1") (pintype "passive"))
      (node (ref "U7") (pin "10") (pinfunction "B4_10") (pintype "bidirectional"))
    )
    (net (code "65") (name "RX") (class "Default")
      (node (ref "J17") (pin "P$3") (pinfunction "3_P$3") (pintype "passive"))
      (node (ref "U1") (pin "20") (pinfunction "PB11_20") (pintype "bidirectional"))
    )
    (net (code "66") (name "SCL1") (class "Default")
      (node (ref "J15") (pin "21") (pinfunction "21_21") (pintype "passive"))
      (node (ref "J15") (pin "22") (pinfunction "22_22") (pintype "passive"))
      (node (ref "J6") (pin "1") (pinfunction "1_1") (pintype "passive"))
      (node (ref "J7") (pin "1") (pinfunction "1_1") (pintype "passive"))
      (node (ref "R12") (pin "8") (pinfunction "8_8") (pintype "passive"))
      (node (ref "U1") (pin "26") (pinfunction "PA17_26") (pintype "bidirectional"))
    )
    (net (code "67") (name "SCL2") (class "Default")
      (node (ref "J16") (pin "P$2") (pinfunction "2_P$2") (pintype "passive"))
      (node (ref "R12") (pin "5") (pinfunction "5_5") (pintype "passive"))
      (node (ref "U1") (pin "22") (pinfunction "PA13_22") (pintype "bidirectional"))
      (node (ref "U4") (pin "23") (pinfunction "SCL_23") (pintype "input"))
    )
    (net (code "68") (name "SDA1") (class "Default")
      (node (ref "J15") (pin "23") (pinfunction "23_23") (pintype "passive"))
      (node (ref "J15") (pin "24") (pinfunction "24_24") (pintype "passive"))
      (node (ref "J6") (pin "2") (pinfunction "2_2") (pintype "passive"))
      (node (ref "J7") (pin "2") (pinfunction "2_2") (pintype "passive"))
      (node (ref "R12") (pin "7") (pinfunction "7_7") (pintype "passive"))
      (node (ref "U1") (pin "25") (pinfunction "PA16_25") (pintype "bidirectional"))
    )
    (net (code "69") (name "SDA2") (class "Default")
      (node (ref "J16") (pin "P$3") (pinfunction "3_P$3") (pintype "passive"))
      (node (ref "R12") (pin "6") (pinfunction "6_6") (pintype "passive"))
      (node (ref "U1") (pin "21") (pinfunction "PA12_21") (pintype "bidirectional"))
      (node (ref "U4") (pin "24") (pinfunction "SDA_24") (pintype "bidirectional"))
    )
    (net (code "70") (name "SERVO1") (class "Default")
      (node (ref "J12") (pin "1") (pinfunction "1_1") (pintype "passive"))
      (node (ref "U1") (pin "2") (pinfunction "PA01_2") (pintype "bidirectional"))
    )
    (net (code "71") (name "SERVO2") (class "Default")
      (node (ref "J12") (pin "4") (pinfunction "4_4") (pintype "passive"))
      (node (ref "U1") (pin "1") (pinfunction "PA00_1") (pintype "bidirectional"))
    )
    (net (code "72") (name "SERVO3") (class "Default")
      (node (ref "J12") (pin "7") (pinfunction "7_7") (pintype "passive"))
      (node (ref "U1") (pin "13") (pinfunction "PA08_13") (pintype "bidirectional"))
    )
    (net (code "73") (name "SERVO4") (class "Default")
      (node (ref "J12") (pin "10") (pinfunction "10_10") (pintype "passive"))
      (node (ref "U1") (pin "14") (pinfunction "PA09_14") (pintype "bidirectional"))
    )
    (net (code "74") (name "SONAR1ECHO") (class "Default")
      (node (ref "U1") (pin "41") (pinfunction "PA28_41") (pintype "bidirectional"))
      (node (ref "U7") (pin "5") (pinfunction "A4_5") (pintype "bidirectional"))
    )
    (net (code "75") (name "SONAR1TRIG") (class "Default")
      (node (ref "J10") (pin "2") (pinfunction "2_2") (pintype "passive"))
      (node (ref "U1") (pin "39") (pinfunction "PA27_39") (pintype "bidirectional"))
    )
    (net (code "76") (name "SONAR2ECHO") (class "Default")
      (node (ref "U1") (pin "47") (pinfunction "PB02_47") (pintype "bidirectional"))
      (node (ref "U7") (pin "4") (pinfunction "A3_4") (pintype "bidirectional"))
    )
    (net (code "77") (name "SONAR2TRIG") (class "Default")
      (node (ref "J9") (pin "2") (pinfunction "2_2") (pintype "passive"))
      (node (ref "U1") (pin "38") (pinfunction "PB23_38") (pintype "bidirectional"))
    )
    (net (code "78") (name "SONAR3ECHO") (class "Default")
      (node (ref "U1") (pin "48") (pinfunction "PB03_48") (pintype "bidirectional"))
      (node (ref "U7") (pin "3") (pinfunction "A2_3") (pintype "bidirectional"))
    )
    (net (code "79") (name "SONAR3TRIG") (class "Default")
      (node (ref "J8") (pin "2") (pinfunction "2_2") (pintype "passive"))
      (node (ref "U1") (pin "37") (pinfunction "PB22_37") (pintype "bidirectional"))
    )
    (net (code "80") (name "SWCLK") (class "Default")
      (node (ref "R11") (pin "2") (pinfunction "2_2") (pintype "passive"))
      (node (ref "TP2") (pin "TP") (pinfunction "TP_TP") (pintype "input"))
      (node (ref "U1") (pin "45") (pinfunction "PA30_45") (pintype "bidirectional"))
    )
    (net (code "81") (name "SWDIO") (class "Default")
      (node (ref "TP3") (pin "TP") (pinfunction "TP_TP") (pintype "input"))
      (node (ref "U1") (pin "46") (pinfunction "PA31_46") (pintype "bidirectional"))
    )
    (net (code "82") (name "TX") (class "Default")
      (node (ref "J17") (pin "P$2") (pinfunction "2_P$2") (pintype "passive"))
      (node (ref "U1") (pin "19") (pinfunction "PB10_19") (pintype "bidirectional"))
    )
    (net (code "83") (name "VSENSE") (class "Default")
      (node (ref "R5") (pin "1") (pinfunction "1_1") (pintype "passive"))
      (node (ref "R6") (pin "1") (pinfunction "1_1") (pintype "passive"))
      (node (ref "U1") (pin "12") (pinfunction "PA07_12") (pintype "bidirectional"))
    )
    (net (code "84") (name "unconnected-(J15-Pad1)") (class "Default")
      (node (ref "J15") (pin "1") (pinfunction "1_1") (pintype "passive"))
    )
    (net (code "85") (name "unconnected-(J15-Pad5)") (class "Default")
      (node (ref "J15") (pin "5") (pinfunction "5_5") (pintype "passive"))
    )
    (net (code "86") (name "unconnected-(J17-4-PadP$4)") (class "Default")
      (node (ref "J17") (pin "P$4") (pinfunction "4_P$4") (pintype "passive"))
    )
    (net (code "87") (name "unconnected-(J17-5-PadP$5)") (class "Default")
      (node (ref "J17") (pin "P$5") (pinfunction "5_P$5") (pintype "passive"))
    )
    (net (code "88") (name "unconnected-(U1-PA03-Pad4)") (class "Default")
      (node (ref "U1") (pin "4") (pinfunction "PA03_4") (pintype "bidirectional"))
    )
    (net (code "89") (name "unconnected-(U1-PA11-Pad16)") (class "Default")
      (node (ref "U1") (pin "16") (pinfunction "PA11_16") (pintype "bidirectional"))
    )
    (net (code "90") (name "unconnected-(U4-AUX_CL-Pad7)") (class "Default")
      (node (ref "U4") (pin "7") (pinfunction "AUX_CL_7") (pintype "input"))
    )
    (net (code "91") (name "unconnected-(U4-AUX_DA-Pad6)") (class "Default")
      (node (ref "U4") (pin "6") (pinfunction "AUX_DA_6") (pintype "bidirectional"))
    )
    (net (code "92") (name "unconnected-(U4-INT-Pad12)") (class "Default")
      (node (ref "U4") (pin "12") (pinfunction "INT_12") (pintype "output"))
    )
    (net (code "93") (name "unconnected-(U4-RESV-Pad19)") (class "Default")
      (node (ref "U4") (pin "19") (pinfunction "RESV_19") (pintype "passive"))
    )
    (net (code "94") (name "unconnected-(U4-RESV-Pad21)") (class "Default")
      (node (ref "U4") (pin "21") (pinfunction "RESV_21") (pintype "passive"))
    )
    (net (code "95") (name "unconnected-(U4-RESV-Pad22)") (class "Default")
      (node (ref "U4") (pin "22") (pinfunction "RESV_22") (pintype "passive"))
    )
    (net (code "96") (name "unconnected-(U7-A1-Pad2)") (class "Default")
      (node (ref "U7") (pin "2") (pinfunction "A1_2") (pintype "bidirectional"))
    )
    (net (code "97") (name "unconnected-(U7-B1-Pad13)") (class "Default")
      (node (ref "U7") (pin "13") (pinfunction "B1_13") (pintype "bidirectional"))
    )
    (net (code "98") (name "unconnected-(U7-NC-Pad9)") (class "Default")
      (node (ref "U7") (pin "9") (pinfunction "NC_9") (pintype "no_connect"))
    )
    (net (code "99") (name "unconnected-(U7-NC_2-Pad6)") (class "Default")
      (node (ref "U7") (pin "6") (pinfunction "NC_2_6") (pintype "no_connect"))
    )
    (net (code "100") (name "unconnected-(USB1-ID-Pad4)") (class "Default")
      (node (ref "USB1") (pin "4") (pinfunction "ID_4") (pintype "bidirectional"))
    )
    (net (code "101") (name "unconnected-(USB1-VCC-Pad1)") (class "Default")
      (node (ref "USB1") (pin "1") (pinfunction "VCC_1") (pintype "bidirectional"))
    )
    (net (code "102") (name "~{RESET}") (class "Default")
      (node (ref "C14") (pin "1") (pinfunction "1_1") (pintype "passive"))
      (node (ref "J14") (pin "1") (pinfunction "1_1") (pintype "passive"))
      (node (ref "J14") (pin "2") (pinfunction "2_2") (pintype "passive"))
      (node (ref "R10") (pin "2") (pinfunction "2_2") (pintype "passive"))
      (node (ref "TP1") (pin "TP") (pinfunction "TP_TP") (pintype "input"))
      (node (ref "U1") (pin "40") (pinfunction "RSTN_40") (pintype "bidirectional"))
    )
  )
)
